# MCU.net
KiCad netlist of a schematic drawn in Altium Designer
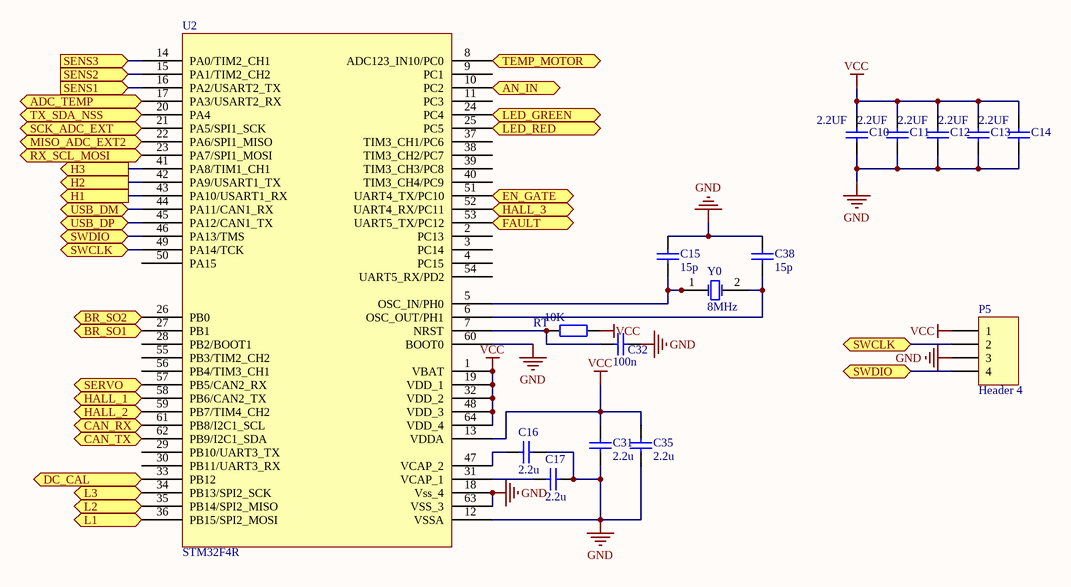
[diagram p0: MCU.SchDoc]

(export (version "E")
  (design (tool "Eeschema 10.0.6"))
  (components
    (comp (ref "C10")
      (value "2.2UF")
      (footprint "C-0603")
      (description "Capacitor")
      (fields (field (name "PUBLISHER") "Altium Limited"))
      (libsource (lib "TAOXUN") (part "CAP"))
    )
    (comp (ref "C11")
      (value "2.2UF")
      (footprint "C-0603")
      (description "Capacitor")
      (fields (field (name "PUBLISHER") "Altium Limited"))
      (libsource (lib "TAOXUN") (part "CAP"))
    )
    (comp (ref "C12")
      (value "2.2UF")
      (footprint "C-0603")
      (description "Capacitor")
      (fields (field (name "PUBLISHER") "Altium Limited"))
      (libsource (lib "TAOXUN") (part "CAP"))
    )
    (comp (ref "C13")
      (value "2.2UF")
      (footprint "C-0603")
      (description "Capacitor")
      (fields (field (name "PUBLISHER") "Altium Limited"))
      (libsource (lib "TAOXUN") (part "CAP"))
    )
    (comp (ref "C14")
      (value "2.2UF")
      (footprint "C-0603")
      (description "Capacitor")
      (fields (field (name "PUBLISHER") "Altium Limited"))
      (libsource (lib "TAOXUN") (part "CAP"))
    )
    (comp (ref "C15")
      (value "15p")
      (footprint "0402")
      (description "Capacitor")
      (fields (field (name "Comment") "15PF") (field (name "PUBLISHER") "Altium Limited"))
      (libsource (lib "TAOXUN") (part "CAP"))
    )
    (comp (ref "C16")
      (value "2.2u")
      (footprint "C-0603")
      (description "Capacitor")
      (fields (field (name "Comment") "2.2UF") (field (name "PUBLISHER") "Altium Limited"))
      (libsource (lib "TAOXUN") (part "CAP"))
    )
    (comp (ref "C17")
      (value "2.2u")
      (footprint "C-0603")
      (description "Capacitor")
      (fields (field (name "Comment") "2.2UF") (field (name "PUBLISHER") "Altium Limited"))
      (libsource (lib "TAOXUN") (part "CAP"))
    )
    (comp (ref "C31")
      (value "2.2u")
      (footprint "C-0603")
      (description "Capacitor")
      (fields (field (name "Comment") "2.2UF") (field (name "PUBLISHER") "Altium Limited"))
      (libsource (lib "TAOXUN") (part "CAP"))
    )
    (comp (ref "C32")
      (value "100n")
      (footprint "C-0603")
      (description "Capacitor")
      (fields (field (name "Comment") "100NF") (field (name "PUBLISHER") "Altium Limited"))
      (libsource (lib "TAOXUN") (part "CAP"))
    )
    (comp (ref "C35")
      (value "2.2u")
      (footprint "C-0603")
      (description "Capacitor")
      (fields (field (name "Comment") "2.2UF") (field (name "PUBLISHER") "Altium Limited"))
      (libsource (lib "TAOXUN") (part "CAP"))
    )
    (comp (ref "C38")
      (value "15p")
      (footprint "0402")
      (description "Capacitor")
      (fields (field (name "Comment") "15PF") (field (name "PUBLISHER") "Altium Limited"))
      (libsource (lib "TAOXUN") (part "CAP"))
    )
    (comp (ref "P5")
      (value "Header 4")
      (footprint "H-1X4")
      (description "Header, 4-Pin")
      (fields (field (name "PUBLISHER") "Altium Limited"))
      (libsource (lib "Miscellaneous Connectors") (part "Header 4"))
    )
    (comp (ref "RT")
      (value "10K")
      (footprint "0603-2")
      (description "贴片电阻")
      (fields (field (name "PUBLISHER") "Altium Limited"))
      (libsource (lib "TAOXUN") (part "Res1"))
    )
    (comp (ref "U2") (value "STM32F4R") (footprint "STM32F4R") (libsource (lib "TAOXUN") (part "STM32F4R")))
    (comp (ref "Y0")
      (value "8MHz")
      (footprint "XTAL_5032")
      (description "Crystal Oscillator")
      (fields (field (name "PUBLISHER") "Altium Limited"))
      (libsource (lib "TAOXUN") (part "XTAL"))
    )
  )
  (nets
    (net (code "1") (name "/ADC_TEMP") (class "Default")
      (node (ref "U2") (pin "17") (pinfunction "PA3/USART2_RX_17") (pintype "passive"))
    )
    (net (code "2") (name "/AN_IN") (class "Default")
      (node (ref "U2") (pin "10") (pinfunction "PC2_10") (pintype "passive"))
    )
    (net (code "3") (name "/BR_SO1") (class "Default")
      (node (ref "U2") (pin "27") (pinfunction "PB1_27") (pintype "passive"))
    )
    (net (code "4") (name "/BR_SO2") (class "Default")
      (node (ref "U2") (pin "26") (pinfunction "PB0_26") (pintype "passive"))
    )
    (net (code "5") (name "/CAN_RX") (class "Default")
      (node (ref "U2") (pin "61") (pinfunction "PB8/I2C1_SCL_61") (pintype "passive"))
    )
    (net (code "6") (name "/CAN_TX") (class "Default")
      (node (ref "U2") (pin "62") (pinfunction "PB9/I2C1_SDA_62") (pintype "passive"))
    )
    (net (code "7") (name "/DC_CAL") (class "Default")
      (node (ref "U2") (pin "33") (pinfunction "PB12_33") (pintype "passive"))
    )
    (net (code "8") (name "/EN_GATE") (class "Default")
      (node (ref "U2") (pin "51") (pinfunction "UART4_TX/PC10_51") (pintype "passive"))
    )
    (net (code "9") (name "/FAULT") (class "Default")
      (node (ref "U2") (pin "53") (pinfunction "UART5_TX/PC12_53") (pintype "passive"))
    )
    (net (code "10") (name "/H1") (class "Default")
      (node (ref "U2") (pin "43") (pinfunction "PA10/USART1_RX_43") (pintype "passive"))
    )
    (net (code "11") (name "/H2") (class "Default")
      (node (ref "U2") (pin "42") (pinfunction "PA9/USART1_TX_42") (pintype "passive"))
    )
    (net (code "12") (name "/H3") (class "Default")
      (node (ref "U2") (pin "41") (pinfunction "PA8/TIM1_CH1_41") (pintype "passive"))
    )
    (net (code "13") (name "/HALL_1") (class "Default")
      (node (ref "U2") (pin "58") (pinfunction "PB6/CAN2_TX_58") (pintype "passive"))
    )
    (net (code "14") (name "/HALL_2") (class "Default")
      (node (ref "U2") (pin "59") (pinfunction "PB7/TIM4_CH2_59") (pintype "passive"))
    )
    (net (code "15") (name "/HALL_3") (class "Default")
      (node (ref "U2") (pin "52") (pinfunction "UART4_RX/PC11_52") (pintype "passive"))
    )
    (net (code "16") (name "/L1") (class "Default")
      (node (ref "U2") (pin "36") (pinfunction "PB15/SPI2_MOSI_36") (pintype "passive"))
    )
    (net (code "17") (name "/L2") (class "Default")
      (node (ref "U2") (pin "35") (pinfunction "PB14/SPI2_MISO_35") (pintype "passive"))
    )
    (net (code "18") (name "/L3") (class "Default")
      (node (ref "U2") (pin "34") (pinfunction "PB13/SPI2_SCK_34") (pintype "passive"))
    )
    (net (code "19") (name "/LED_GREEN") (class "Default")
      (node (ref "U2") (pin "24") (pinfunction "PC4_24") (pintype "passive"))
    )
    (net (code "20") (name "/LED_RED") (class "Default")
      (node (ref "U2") (pin "25") (pinfunction "PC5_25") (pintype "passive"))
    )
    (net (code "21") (name "/MISO_ADC_EXT2") (class "Default")
      (node (ref "U2") (pin "22") (pinfunction "PA6/SPI1_MISO_22") (pintype "passive"))
    )
    (net (code "22") (name "/RX_SCL_MOSI") (class "Default")
      (node (ref "U2") (pin "23") (pinfunction "PA7/SPI1_MOSI_23") (pintype "passive"))
    )
    (net (code "23") (name "/SCK_ADC_EXT") (class "Default")
      (node (ref "U2") (pin "21") (pinfunction "PA5/SPI1_SCK_21") (pintype "passive"))
    )
    (net (code "24") (name "/SENS1") (class "Default")
      (node (ref "U2") (pin "16") (pinfunction "PA2/USART2_TX_16") (pintype "passive"))
    )
    (net (code "25") (name "/SENS2") (class "Default")
      (node (ref "U2") (pin "15") (pinfunction "PA1/TIM2_CH2_15") (pintype "passive"))
    )
    (net (code "26") (name "/SENS3") (class "Default")
      (node (ref "U2") (pin "14") (pinfunction "PA0/TIM2_CH1_14") (pintype "passive"))
    )
    (net (code "27") (name "/SERVO") (class "Default")
      (node (ref "U2") (pin "57") (pinfunction "PB5/CAN2_RX_57") (pintype "passive"))
    )
    (net (code "28") (name "/SWCLK") (class "Default")
      (node (ref "P5") (pin "2") (pinfunction "2_2") (pintype "passive"))
      (node (ref "U2") (pin "49") (pinfunction "PA14/TCK_49") (pintype "passive"))
    )
    (net (code "29") (name "/SWDIO") (class "Default")
      (node (ref "P5") (pin "4") (pinfunction "4_4") (pintype "passive"))
      (node (ref "U2") (pin "46") (pinfunction "PA13/TMS_46") (pintype "passive"))
    )
    (net (code "30") (name "/TEMP_MOTOR") (class "Default")
      (node (ref "U2") (pin "8") (pinfunction "ADC123_IN10/PC0_8") (pintype "passive"))
    )
    (net (code "31") (name "/TX_SDA_NSS") (class "Default")
      (node (ref "U2") (pin "20") (pinfunction "PA4_20") (pintype "passive"))
    )
    (net (code "32") (name "/USB_DM") (class "Default")
      (node (ref "U2") (pin "44") (pinfunction "PA11/CAN1_RX_44") (pintype "passive"))
    )
    (net (code "33") (name "/USB_DP") (class "Default")
      (node (ref "U2") (pin "45") (pinfunction "PA12/CAN1_TX_45") (pintype "passive"))
    )
    (net (code "34") (name "GND") (class "Default")
      (node (ref "C10") (pin "1") (pinfunction "1_1") (pintype "passive"))
      (node (ref "C11") (pin "1") (pinfunction "1_1") (pintype "passive"))
      (node (ref "C12") (pin "1") (pinfunction "1_1") (pintype "passive"))
      (node (ref "C13") (pin "1") (pinfunction "1_1") (pintype "passive"))
      (node (ref "C14") (pin "1") (pinfunction "1_1") (pintype "passive"))
      (node (ref "C15") (pin "2") (pinfunction "2_2") (pintype "passive"))
      (node (ref "C16") (pin "1") (pinfunction "1_1") (pintype "passive"))
      (node (ref "C17") (pin "1") (pinfunction "1_1") (pintype "passive"))
      (node (ref "C31") (pin "1") (pinfunction "1_1") (pintype "passive"))
      (node (ref "C32") (pin "1") (pinfunction "1_1") (pintype "passive"))
      (node (ref "C35") (pin "1") (pinfunction "1_1") (pintype "passive"))
      (node (ref "C38") (pin "2") (pinfunction "2_2") (pintype "passive"))
      (node (ref "P5") (pin "3") (pinfunction "3_3") (pintype "passive"))
      (node (ref "U2") (pin "12") (pinfunction "VSSA_12") (pintype "passive"))
      (node (ref "U2") (pin "18") (pinfunction "Vss_4_18") (pintype "passive"))
      (node (ref "U2") (pin "60") (pinfunction "BOOT0_60") (pintype "passive"))
      (node (ref "U2") (pin "63") (pinfunction "VSS_3_63") (pintype "passive"))
    )
    (net (code "35") (name "Net-(U2-NRST)") (class "Default")
      (node (ref "C32") (pin "2") (pinfunction "2_2") (pintype "passive"))
      (node (ref "RT") (pin "1") (pinfunction "1_1") (pintype "passive"))
      (node (ref "U2") (pin "7") (pinfunction "NRST_7") (pintype "passive"))
    )
    (net (code "36") (name "Net-(U2-OSC_IN{slash}PH0)") (class "Default")
      (node (ref "C15") (pin "1") (pinfunction "1_1") (pintype "passive"))
      (node (ref "U2") (pin "5") (pinfunction "OSC_IN/PH0_5") (pintype "passive"))
      (node (ref "Y0") (pin "1") (pinfunction "OSC1_1") (pintype "passive"))
    )
    (net (code "37") (name "Net-(U2-OSC_OUT{slash}PH1)") (class "Default")
      (node (ref "C38") (pin "1") (pinfunction "1_1") (pintype "passive"))
      (node (ref "U2") (pin "6") (pinfunction "OSC_OUT/PH1_6") (pintype "passive"))
      (node (ref "Y0") (pin "2") (pinfunction "OSC2_2") (pintype "passive"))
    )
    (net (code "38") (name "Net-(U2-VCAP_1)") (class "Default")
      (node (ref "C17") (pin "2") (pinfunction "2_2") (pintype "passive"))
      (node (ref "U2") (pin "31") (pinfunction "VCAP_1_31") (pintype "passive"))
    )
    (net (code "39") (name "Net-(U2-VCAP_2)") (class "Default")
      (node (ref "C16") (pin "2") (pinfunction "2_2") (pintype "passive"))
      (node (ref "U2") (pin "47") (pinfunction "VCAP_2_47") (pintype "passive"))
    )
    (net (code "40") (name "VCC") (class "Default")
      (node (ref "C10") (pin "2") (pinfunction "2_2") (pintype "passive"))
      (node (ref "C11") (pin "2") (pinfunction "2_2") (pintype "passive"))
      (node (ref "C12") (pin "2") (pinfunction "2_2") (pintype "passive"))
      (node (ref "C13") (pin "2") (pinfunction "2_2") (pintype "passive"))
      (node (ref "C14") (pin "2") (pinfunction "2_2") (pintype "passive"))
      (node (ref "C31") (pin "2") (pinfunction "2_2") (pintype "passive"))
      (node (ref "C35") (pin "2") (pinfunction "2_2") (pintype "passive"))
      (node (ref "P5") (pin "1") (pinfunction "1_1") (pintype "passive"))
      (node (ref "RT") (pin "2") (pinfunction "2_2") (pintype "passive"))
      (node (ref "U2") (pin "1") (pinfunction "VBAT_1") (pintype "passive"))
      (node (ref "U2") (pin "13") (pinfunction "VDDA_13") (pintype "passive"))
      (node (ref "U2") (pin "19") (pinfunction "VDD_1_19") (pintype "passive"))
      (node (ref "U2") (pin "32") (pinfunction "VDD_2_32") (pintype "passive"))
      (node (ref "U2") (pin "48") (pinfunction "VDD_3_48") (pintype "passive"))
      (node (ref "U2") (pin "64") (pinfunction "VDD_4_64") (pintype "passive"))
    )
    (net (code "41") (name "unconnected-(U2-PA15-Pad50)") (class "Default")
      (node (ref "U2") (pin "50") (pinfunction "PA15_50") (pintype "passive"))
    )
    (net (code "42") (name "unconnected-(U2-PB2{slash}BOOT1-Pad28)") (class "Default")
      (node (ref "U2") (pin "28") (pinfunction "PB2/BOOT1_28") (pintype "passive"))
    )
    (net (code "43") (name "unconnected-(U2-PB3{slash}TIM2_CH2-Pad55)") (class "Default")
      (node (ref "U2") (pin "55") (pinfunction "PB3/TIM2_CH2_55") (pintype "passive"))
    )
    (net (code "44") (name "unconnected-(U2-PB4{slash}TIM3_CH1-Pad56)") (class "Default")
      (node (ref "U2") (pin "56") (pinfunction "PB4/TIM3_CH1_56") (pintype "passive"))
    )
    (net (code "45") (name "unconnected-(U2-PB10{slash}UART3_TX-Pad29)") (class "Default")
      (node (ref "U2") (pin "29") (pinfunction "PB10/UART3_TX_29") (pintype "passive"))
    )
    (net (code "46") (name "unconnected-(U2-PB11{slash}UART3_RX-Pad30)") (class "Default")
      (node (ref "U2") (pin "30") (pinfunction "PB11/UART3_RX_30") (pintype "passive"))
    )
    (net (code "47") (name "unconnected-(U2-PC1-Pad9)") (class "Default")
      (node (ref "U2") (pin "9") (pinfunction "PC1_9") (pintype "passive"))
    )
    (net (code "48") (name "unconnected-(U2-PC3-Pad11)") (class "Default")
      (node (ref "U2") (pin "11") (pinfunction "PC3_11") (pintype "passive"))
    )
    (net (code "49") (name "unconnected-(U2-PC13-Pad2)") (class "Default")
      (node (ref "U2") (pin "2") (pinfunction "PC13_2") (pintype "passive"))
    )
    (net (code "50") (name "unconnected-(U2-PC14-Pad3)") (class "Default")
      (node (ref "U2") (pin "3") (pinfunction "PC14_3") (pintype "passive"))
    )
    (net (code "51") (name "unconnected-(U2-PC15-Pad4)") (class "Default")
      (node (ref "U2") (pin "4") (pinfunction "PC15_4") (pintype "passive"))
    )
    (net (code "52") (name "unconnected-(U2-TIM3_CH1{slash}PC6-Pad37)") (class "Default")
      (node (ref "U2") (pin "37") (pinfunction "TIM3_CH1/PC6_37") (pintype "passive"))
    )
    (net (code "53") (name "unconnected-(U2-TIM3_CH2{slash}PC7-Pad38)") (class "Default")
      (node (ref "U2") (pin "38") (pinfunction "TIM3_CH2/PC7_38") (pintype "passive"))
    )
    (net (code "54") (name "unconnected-(U2-TIM3_CH3{slash}PC8-Pad39)") (class "Default")
      (node (ref "U2") (pin "39") (pinfunction "TIM3_CH3/PC8_39") (pintype "passive"))
    )
    (net (code "55") (name "unconnected-(U2-TIM3_CH4{slash}PC9-Pad40)") (class "Default")
      (node (ref "U2") (pin "40") (pinfunction "TIM3_CH4/PC9_40") (pintype "passive"))
    )
    (net (code "56") (name "unconnected-(U2-UART5_RX{slash}PD2-Pad54)") (class "Default")
      (node (ref "U2") (pin "54") (pinfunction "UART5_RX/PD2_54") (pintype "passive"))
    )
  )
)
